# led_board.net
KiCad netlist of a schematic drawn in Altium Designer
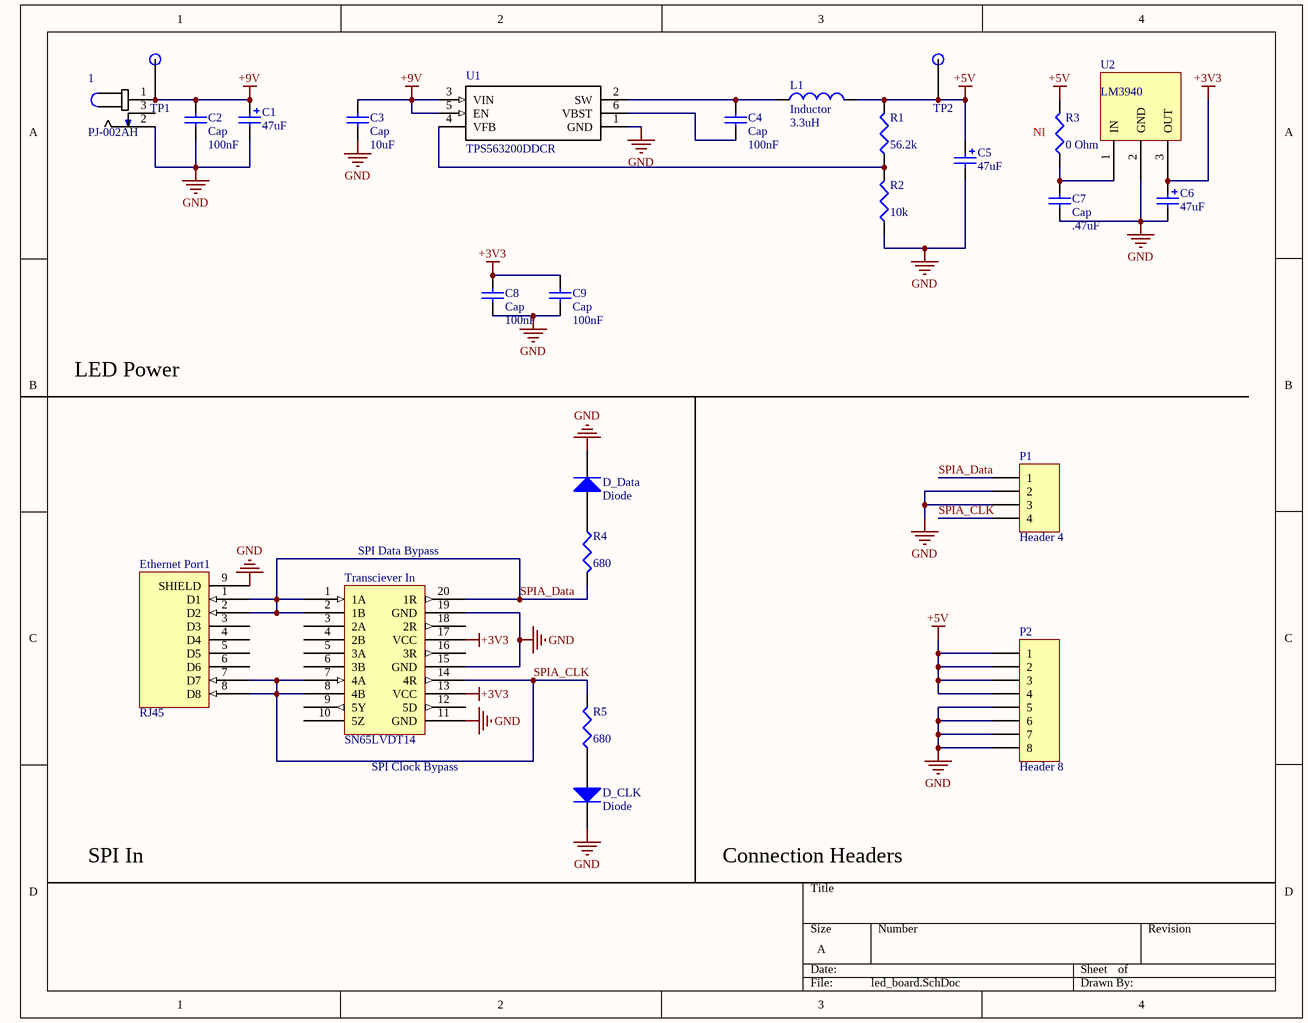
[diagram p0: led_board.SchDoc]

(export (version "E")
  (design (tool "Eeschema 10.0.6"))
  (components
    (comp (ref "1") (value "PJ-002AH") (footprint "PJ-002AH") (libsource (lib "PJ-002AH") (part "PJ-002AH")))
    (comp (ref "C1")
      (value "47uF")
      (footprint "Pol Cap 5mm-10mm")
      (description "UUQ1C470MCL1GB")
      (libsource (lib "Senior_SCH_Lib") (part "UUQ1C470MCL1GB"))
    )
    (comp (ref "C2")
      (value "Cap")
      (footprint "HDR1X2")
      (description "Capacitor")
      (fields (field (name "ALTIUM_VALUE") "100nF") (field (name "PUBLISHER") "Altium Limited"))
      (libsource (lib "Miscellaneous Devices") (part "Cap"))
    )
    (comp (ref "C3")
      (value "Cap")
      (footprint "HDR1X2")
      (description "Capacitor")
      (fields (field (name "ALTIUM_VALUE") "10uF") (field (name "PUBLISHER") "Altium Limited"))
      (libsource (lib "Miscellaneous Devices") (part "Cap"))
    )
    (comp (ref "C4")
      (value "Cap")
      (footprint "HDR1X2")
      (description "Capacitor")
      (fields (field (name "ALTIUM_VALUE") "100nF") (field (name "PUBLISHER") "Altium Limited"))
      (libsource (lib "Miscellaneous Devices") (part "Cap"))
    )
    (comp (ref "C5")
      (value "47uF")
      (footprint "HDR1X2")
      (description "UUQ1C470MCL1GB")
      (libsource (lib "Senior_SCH_Lib") (part "UUQ1C470MCL1GB"))
    )
    (comp (ref "C6")
      (value "47uF")
      (footprint "HDR1X2")
      (description "UUQ1C470MCL1GB")
      (libsource (lib "Senior_SCH_Lib") (part "UUQ1C470MCL1GB"))
    )
    (comp (ref "C7")
      (value "Cap")
      (footprint "HDR1X2")
      (description "Capacitor")
      (fields (field (name "ALTIUM_VALUE") ".47uF") (field (name "PUBLISHER") "Altium Limited"))
      (libsource (lib "Miscellaneous Devices") (part "Cap"))
    )
    (comp (ref "C8")
      (value "Cap")
      (footprint "HDR1X2")
      (description "Capacitor")
      (fields (field (name "ALTIUM_VALUE") "100nF") (field (name "PUBLISHER") "Altium Limited"))
      (libsource (lib "Miscellaneous Devices") (part "Cap"))
    )
    (comp (ref "C9")
      (value "Cap")
      (footprint "HDR1X2")
      (description "Capacitor")
      (fields (field (name "ALTIUM_VALUE") "100nF") (field (name "PUBLISHER") "Altium Limited"))
      (libsource (lib "Miscellaneous Devices") (part "Cap"))
    )
    (comp (ref "D_CLK")
      (value "Diode")
      (footprint "C1206")
      (description "Default Diode")
      (fields (field (name "PUBLISHER") "Altium Limited"))
      (libsource (lib "Miscellaneous Devices") (part "Diode"))
    )
    (comp (ref "D_Data")
      (value "Diode")
      (footprint "C1206")
      (description "Default Diode")
      (fields (field (name "PUBLISHER") "Altium Limited"))
      (libsource (lib "Miscellaneous Devices") (part "Diode"))
    )
    (comp (ref "Ethernet Port1")
      (value "RJ45")
      (footprint "RJ45")
      (libsource (lib "Senior_SCH_Lib") (part "RJ45"))
    )
    (comp (ref "L1")
      (value "Inductor")
      (footprint "RB5-10.5")
      (fields (field (name "ALTIUM_VALUE") "3.3uH") (field (name "PUBLISHER") "Altium Limited"))
      (libsource (lib "Miscellaneous Devices") (part "Inductor"))
    )
    (comp (ref "P1")
      (value "Header 4")
      (footprint "HDR1X4")
      (description "Header, 4-Pin")
      (fields (field (name "PUBLISHER") "Altium Limited"))
      (libsource (lib "Miscellaneous Connectors") (part "Header 4"))
    )
    (comp (ref "P2")
      (value "Header 8")
      (footprint "HDR1X8")
      (description "Header, 8-Pin")
      (fields (field (name "PUBLISHER") "Altium Limited"))
      (libsource (lib "Miscellaneous Connectors") (part "Header 8"))
    )
    (comp (ref "R1")
      (value "56.2k")
      (footprint "RAD-0.2")
      (description "Resistor")
      (fields (field (name "PUBLISHER") "Altium Limited"))
      (libsource (lib "Miscellaneous Devices") (part "Res3"))
    )
    (comp (ref "R2")
      (value "10k")
      (footprint "RAD-0.2")
      (description "Resistor")
      (fields (field (name "PUBLISHER") "Altium Limited"))
      (libsource (lib "Miscellaneous Devices") (part "Res3"))
    )
    (comp (ref "R3")
      (value "0 Ohm")
      (footprint "HDR1X2")
      (description "Resistor")
      (fields (field (name "PUBLISHER") "Altium Limited"))
      (libsource (lib "Miscellaneous Devices") (part "Res3"))
    )
    (comp (ref "R4")
      (value "680")
      (footprint "RAD-0.2")
      (description "Resistor")
      (fields (field (name "PUBLISHER") "Altium Limited"))
      (libsource (lib "Miscellaneous Devices") (part "Res3"))
    )
    (comp (ref "R5")
      (value "680")
      (footprint "RAD-0.2")
      (description "Resistor")
      (fields (field (name "PUBLISHER") "Altium Limited"))
      (libsource (lib "Miscellaneous Devices") (part "Res3"))
    )
    (comp (ref "TP1")
      (value "Test Point")
      (footprint "Test Point")
      (libsource (lib "Senior_SCH_Lib") (part "Test Point"))
    )
    (comp (ref "TP2")
      (value "Test Point")
      (footprint "Test Point")
      (libsource (lib "Senior_SCH_Lib") (part "Test Point"))
    )
    (comp (ref "Transciever In")
      (value "SN65LVDT14")
      (footprint "SN65LVDT41")
      (libsource (lib "Senior_SCH_Lib") (part "SN65LVDT14"))
    )
    (comp (ref "U1")
      (value "TPS563200DDCR")
      (footprint "DDC0006A")
      (description "17 V Input, 3A Synchronous Step-Down Regulator in SOT-23 with Advanced Eco-mode? 6-SOT -40 to 85")
      (fields (field (name "DIGI-KEY_PART_NUMBER") "296-43663-1-ND") (field (name "MF") "Texas Instruments"))
      (libsource (lib "TPS563200DDCR") (part "TPS563200DDCR"))
    )
    (comp (ref "U2") (value "LM3940") (footprint "LM3940") (libsource (lib "Senior_SCH_Lib") (part "LM3940")))
  )
  (nets
    (net (code "1") (name "+3V3") (class "Default")
      (node (ref "C6") (pin "1") (pinfunction "1_1") (pintype "passive"))
      (node (ref "C8") (pin "1") (pinfunction "1_1") (pintype "passive"))
      (node (ref "C9") (pin "1") (pinfunction "1_1") (pintype "passive"))
      (node (ref "Transciever In") (pin "13") (pinfunction "VCC_13") (pintype "power_in"))
      (node (ref "Transciever In") (pin "17") (pinfunction "VCC_17") (pintype "power_in"))
      (node (ref "U2") (pin "3") (pinfunction "OUT_3") (pintype "passive"))
    )
    (net (code "2") (name "+5V") (class "Default")
      (node (ref "C5") (pin "1") (pinfunction "1_1") (pintype "passive"))
      (node (ref "L1") (pin "2") (pinfunction "2_2") (pintype "passive"))
      (node (ref "P2") (pin "1") (pinfunction "1_1") (pintype "passive"))
      (node (ref "P2") (pin "2") (pinfunction "2_2") (pintype "passive"))
      (node (ref "P2") (pin "3") (pinfunction "3_3") (pintype "passive"))
      (node (ref "P2") (pin "4") (pinfunction "4_4") (pintype "passive"))
      (node (ref "R1") (pin "2") (pinfunction "2_2") (pintype "passive"))
      (node (ref "R3") (pin "2") (pinfunction "2_2") (pintype "passive"))
      (node (ref "TP2") (pin "TP") (pinfunction "Test_Point_TP") (pintype "passive"))
    )
    (net (code "3") (name "+9V") (class "Default")
      (node (ref "1") (pin "1") (pinfunction "1_1") (pintype "power_in"))
      (node (ref "C1") (pin "1") (pinfunction "1_1") (pintype "passive"))
      (node (ref "C2") (pin "2") (pinfunction "2_2") (pintype "passive"))
      (node (ref "C3") (pin "2") (pinfunction "2_2") (pintype "passive"))
      (node (ref "TP1") (pin "TP") (pinfunction "Test_Point_TP") (pintype "passive"))
      (node (ref "U1") (pin "3") (pinfunction "VIN_3") (pintype "input"))
      (node (ref "U1") (pin "5") (pinfunction "EN_5") (pintype "input"))
    )
    (net (code "4") (name "/SPIA_CLK") (class "Default")
      (node (ref "Ethernet Port1") (pin "7") (pinfunction "D7_7") (pintype "input"))
      (node (ref "Ethernet Port1") (pin "8") (pinfunction "D8_8") (pintype "input"))
      (node (ref "P1") (pin "4") (pinfunction "4_4") (pintype "passive"))
      (node (ref "R5") (pin "2") (pinfunction "2_2") (pintype "passive"))
      (node (ref "Transciever In") (pin "14") (pinfunction "4R_14") (pintype "output"))
      (node (ref "Transciever In") (pin "7") (pinfunction "4A_7") (pintype "input"))
      (node (ref "Transciever In") (pin "8") (pinfunction "4B_8") (pintype "power_in"))
    )
    (net (code "5") (name "/SPIA_Data") (class "Default")
      (node (ref "Ethernet Port1") (pin "1") (pinfunction "D1_1") (pintype "input"))
      (node (ref "Ethernet Port1") (pin "2") (pinfunction "D2_2") (pintype "input"))
      (node (ref "P1") (pin "1") (pinfunction "1_1") (pintype "passive"))
      (node (ref "R4") (pin "2") (pinfunction "2_2") (pintype "passive"))
      (node (ref "Transciever In") (pin "1") (pinfunction "1A_1") (pintype "input"))
      (node (ref "Transciever In") (pin "2") (pinfunction "1B_2") (pintype "power_in"))
      (node (ref "Transciever In") (pin "20") (pinfunction "1R_20") (pintype "output"))
    )
    (net (code "6") (name "GND") (class "Default")
      (node (ref "1") (pin "2") (pinfunction "2_2") (pintype "passive"))
      (node (ref "C1") (pin "2") (pinfunction "2_2") (pintype "passive"))
      (node (ref "C2") (pin "1") (pinfunction "1_1") (pintype "passive"))
      (node (ref "C3") (pin "1") (pinfunction "1_1") (pintype "passive"))
      (node (ref "C5") (pin "2") (pinfunction "2_2") (pintype "passive"))
      (node (ref "C6") (pin "2") (pinfunction "2_2") (pintype "passive"))
      (node (ref "C7") (pin "1") (pinfunction "1_1") (pintype "passive"))
      (node (ref "C8") (pin "2") (pinfunction "2_2") (pintype "passive"))
      (node (ref "C9") (pin "2") (pinfunction "2_2") (pintype "passive"))
      (node (ref "D_CLK") (pin "2") (pinfunction "K_2") (pintype "passive"))
      (node (ref "D_Data") (pin "2") (pinfunction "K_2") (pintype "passive"))
      (node (ref "Ethernet Port1") (pin "9") (pinfunction "SHIELD_9") (pintype "power_in"))
      (node (ref "P1") (pin "2") (pinfunction "2_2") (pintype "passive"))
      (node (ref "P1") (pin "3") (pinfunction "3_3") (pintype "passive"))
      (node (ref "P2") (pin "5") (pinfunction "5_5") (pintype "passive"))
      (node (ref "P2") (pin "6") (pinfunction "6_6") (pintype "passive"))
      (node (ref "P2") (pin "7") (pinfunction "7_7") (pintype "passive"))
      (node (ref "P2") (pin "8") (pinfunction "8_8") (pintype "passive"))
      (node (ref "R2") (pin "1") (pinfunction "1_1") (pintype "passive"))
      (node (ref "Transciever In") (pin "11") (pinfunction "GND_11") (pintype "power_in"))
      (node (ref "Transciever In") (pin "15") (pinfunction "GND_15") (pintype "power_in"))
      (node (ref "Transciever In") (pin "19") (pinfunction "GND_19") (pintype "power_in"))
      (node (ref "U1") (pin "1") (pinfunction "GND_1") (pintype "power_in"))
      (node (ref "U2") (pin "2") (pinfunction "GND_2") (pintype "passive"))
    )
    (net (code "7") (name "Net-(D_CLK-A)") (class "Default")
      (node (ref "D_CLK") (pin "1") (pinfunction "A_1") (pintype "passive"))
      (node (ref "R5") (pin "1") (pinfunction "1_1") (pintype "passive"))
    )
    (net (code "8") (name "Net-(D_Data-A)") (class "Default")
      (node (ref "D_Data") (pin "1") (pinfunction "A_1") (pintype "passive"))
      (node (ref "R4") (pin "1") (pinfunction "1_1") (pintype "passive"))
    )
    (net (code "9") (name "Net-(U1-SW)") (class "Default")
      (node (ref "C4") (pin "2") (pinfunction "2_2") (pintype "passive"))
      (node (ref "L1") (pin "1") (pinfunction "1_1") (pintype "passive"))
      (node (ref "U1") (pin "2") (pinfunction "SW_2") (pintype "passive"))
    )
    (net (code "10") (name "Net-(U1-VBST)") (class "Default")
      (node (ref "C4") (pin "1") (pinfunction "1_1") (pintype "passive"))
      (node (ref "U1") (pin "6") (pinfunction "VBST_6") (pintype "passive"))
    )
    (net (code "11") (name "Net-(U1-VFB)") (class "Default")
      (node (ref "R1") (pin "1") (pinfunction "1_1") (pintype "passive"))
      (node (ref "R2") (pin "2") (pinfunction "2_2") (pintype "passive"))
      (node (ref "U1") (pin "4") (pinfunction "VFB_4") (pintype "passive"))
    )
    (net (code "12") (name "Net-(U2-IN)") (class "Default")
      (node (ref "C7") (pin "2") (pinfunction "2_2") (pintype "passive"))
      (node (ref "R3") (pin "1") (pinfunction "1_1") (pintype "passive"))
      (node (ref "U2") (pin "1") (pinfunction "IN_1") (pintype "passive"))
    )
    (net (code "13") (name "unconnected-(1-Pad3)") (class "Default")
      (node (ref "1") (pin "3") (pinfunction "3_3") (pintype "passive"))
    )
    (net (code "14") (name "unconnected-(Ethernet Port1-D3-Pad3)") (class "Default")
      (node (ref "Ethernet Port1") (pin "3") (pinfunction "D3_3") (pintype "passive"))
    )
    (net (code "15") (name "unconnected-(Ethernet Port1-D4-Pad4)") (class "Default")
      (node (ref "Ethernet Port1") (pin "4") (pinfunction "D4_4") (pintype "passive"))
    )
    (net (code "16") (name "unconnected-(Ethernet Port1-D5-Pad5)") (class "Default")
      (node (ref "Ethernet Port1") (pin "5") (pinfunction "D5_5") (pintype "passive"))
    )
    (net (code "17") (name "unconnected-(Ethernet Port1-D6-Pad6)") (class "Default")
      (node (ref "Ethernet Port1") (pin "6") (pinfunction "D6_6") (pintype "passive"))
    )
    (net (code "18") (name "unconnected-(Transciever In-2A-Pad3)") (class "Default")
      (node (ref "Transciever In") (pin "3") (pinfunction "2A_3") (pintype "passive"))
    )
    (net (code "19") (name "unconnected-(Transciever In-2B-Pad4)") (class "Default")
      (node (ref "Transciever In") (pin "4") (pinfunction "2B_4") (pintype "passive"))
    )
    (net (code "20") (name "unconnected-(Transciever In-2R-Pad18)") (class "Default")
      (node (ref "Transciever In") (pin "18") (pinfunction "2R_18") (pintype "output"))
    )
    (net (code "21") (name "unconnected-(Transciever In-3A-Pad5)") (class "Default")
      (node (ref "Transciever In") (pin "5") (pinfunction "3A_5") (pintype "passive"))
    )
    (net (code "22") (name "unconnected-(Transciever In-3B-Pad6)") (class "Default")
      (node (ref "Transciever In") (pin "6") (pinfunction "3B_6") (pintype "passive"))
    )
    (net (code "23") (name "unconnected-(Transciever In-3R-Pad16)") (class "Default")
      (node (ref "Transciever In") (pin "16") (pinfunction "3R_16") (pintype "output"))
    )
    (net (code "24") (name "unconnected-(Transciever In-5D-Pad12)") (class "Default")
      (node (ref "Transciever In") (pin "12") (pinfunction "5D_12") (pintype "output"))
    )
    (net (code "25") (name "unconnected-(Transciever In-5Y-Pad9)") (class "Default")
      (node (ref "Transciever In") (pin "9") (pinfunction "5Y_9") (pintype "output"))
    )
    (net (code "26") (name "unconnected-(Transciever In-5Z-Pad10)") (class "Default")
      (node (ref "Transciever In") (pin "10") (pinfunction "5Z_10") (pintype "power_in"))
    )
  )
)
